# curveTracerRev4.net
KiCad netlist of a schematic drawn in EAGLE
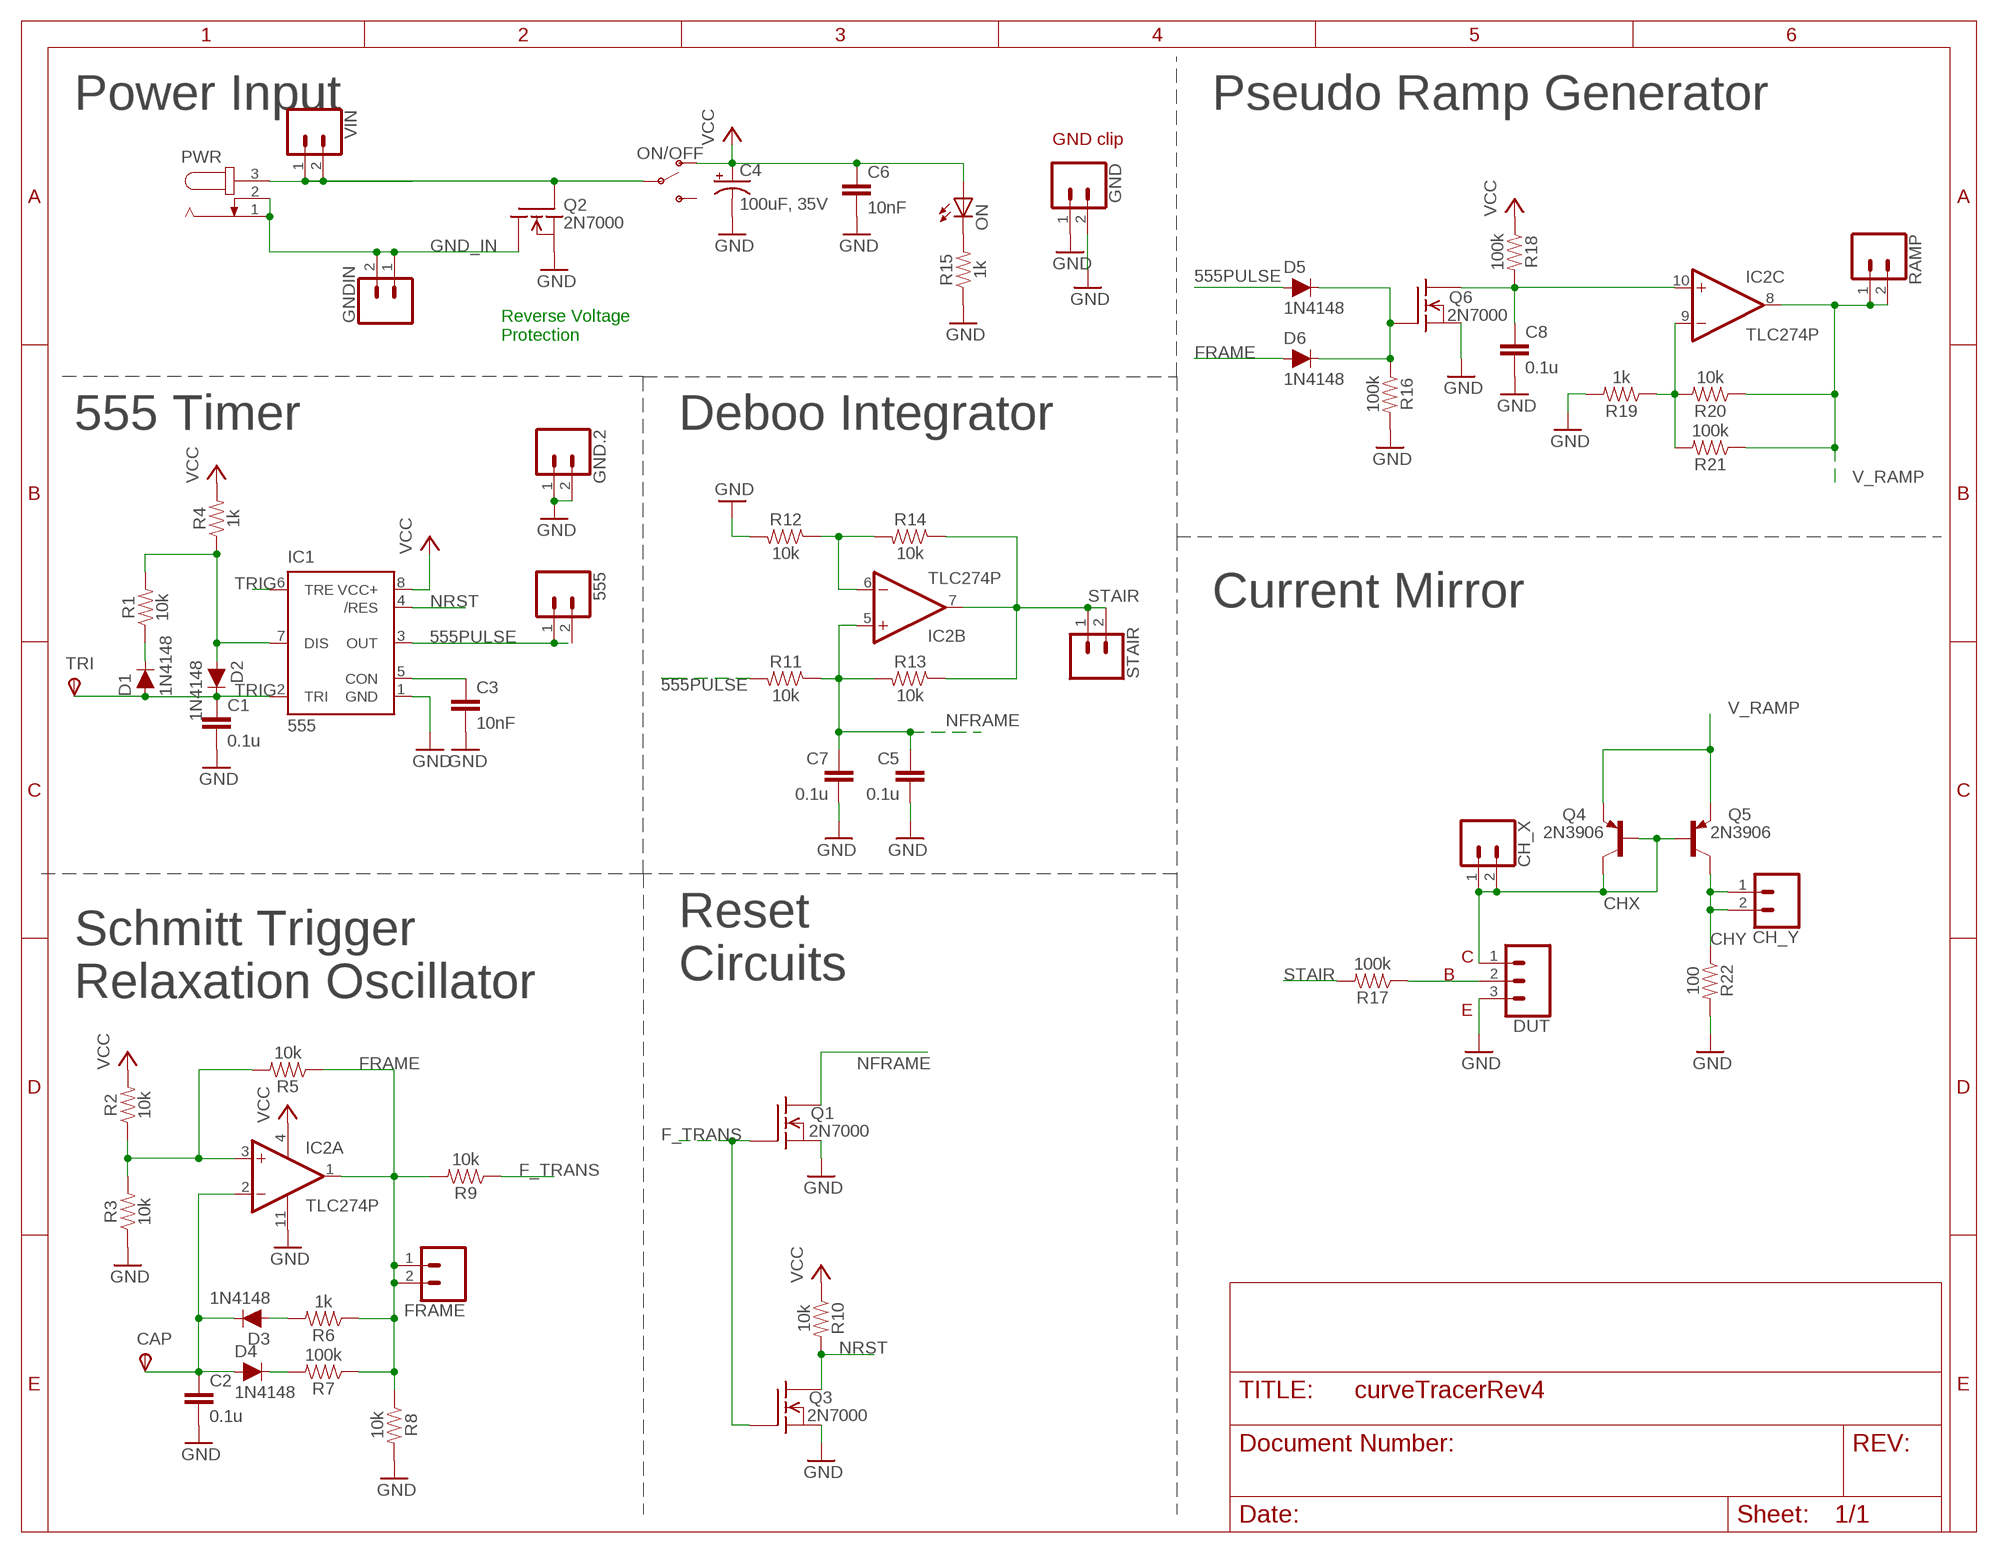
[diagram p0: schematic, sheet 1]

(export (version "E")
  (design (tool "Eeschema 10.0.6"))
  (components
    (comp (ref "555")
      (value "CONN_02")
      (footprint "eagle-import:1X02")
      (libsource (lib "eagle-import") (part "CONN_02"))
    )
    (comp (ref "C1")
      (value "0.1u")
      (footprint "eagle-import:C050-024X044")
      (libsource (lib "eagle-import") (part "C-EU050-024X044"))
    )
    (comp (ref "C2")
      (value "0.1u")
      (footprint "eagle-import:C050-024X044")
      (libsource (lib "eagle-import") (part "C-EU050-024X044"))
    )
    (comp (ref "C3")
      (value "10nF")
      (footprint "eagle-import:C050-024X044")
      (libsource (lib "eagle-import") (part "C-EU050-024X044"))
    )
    (comp (ref "C4")
      (value "100uF, 35V")
      (footprint "eagle-import:E2,5-6")
      (libsource (lib "eagle-import") (part "CPOL-USE2.5-6"))
    )
    (comp (ref "C5")
      (value "0.1u")
      (footprint "eagle-import:C050-024X044")
      (libsource (lib "eagle-import") (part "C-EU050-024X044"))
    )
    (comp (ref "C6")
      (value "10nF")
      (footprint "eagle-import:C050-024X044")
      (libsource (lib "eagle-import") (part "C-EU050-024X044"))
    )
    (comp (ref "C7")
      (value "0.1u")
      (footprint "eagle-import:C050-024X044")
      (libsource (lib "eagle-import") (part "C-EU050-024X044"))
    )
    (comp (ref "C8")
      (value "0.1u")
      (footprint "eagle-import:C050-024X044")
      (libsource (lib "eagle-import") (part "C-EU050-024X044"))
    )
    (comp (ref "CAP")
      (value "TPSPAD1-13Y")
      (footprint "eagle-import:P1-13Y")
      (libsource (lib "eagle-import") (part "TPSPAD1-13Y"))
    )
    (comp (ref "CH_X")
      (value "CONN_02")
      (footprint "eagle-import:1X02")
      (libsource (lib "eagle-import") (part "CONN_02"))
    )
    (comp (ref "CH_Y")
      (value "CONN_02")
      (footprint "eagle-import:1X02")
      (libsource (lib "eagle-import") (part "CONN_02"))
    )
    (comp (ref "D1")
      (value "1N4148")
      (footprint "eagle-import:DIODE-1N4148")
      (libsource (lib "eagle-import") (part "DIODE-1N4148"))
    )
    (comp (ref "D2")
      (value "1N4148")
      (footprint "eagle-import:DIODE-1N4148")
      (libsource (lib "eagle-import") (part "DIODE-1N4148"))
    )
    (comp (ref "D3")
      (value "1N4148")
      (footprint "eagle-import:DIODE-1N4148")
      (libsource (lib "eagle-import") (part "DIODE-1N4148"))
    )
    (comp (ref "D4")
      (value "1N4148")
      (footprint "eagle-import:DIODE-1N4148")
      (libsource (lib "eagle-import") (part "DIODE-1N4148"))
    )
    (comp (ref "D5")
      (value "1N4148")
      (footprint "eagle-import:DIODE-1N4148")
      (libsource (lib "eagle-import") (part "DIODE-1N4148"))
    )
    (comp (ref "D6")
      (value "1N4148")
      (footprint "eagle-import:DIODE-1N4148")
      (libsource (lib "eagle-import") (part "DIODE-1N4148"))
    )
    (comp (ref "DUT")
      (value "CONN_03LOCK_LONGPADS")
      (footprint "eagle-import:1X03_LOCK_LONGPADS")
      (libsource (lib "eagle-import") (part "CONN_03LOCK_LONGPADS"))
    )
    (comp (ref "FRAME")
      (value "CONN_02")
      (footprint "eagle-import:1X02")
      (libsource (lib "eagle-import") (part "CONN_02"))
    )
    (comp (ref "GND")
      (value "CONN_02")
      (footprint "eagle-import:1X02")
      (libsource (lib "eagle-import") (part "CONN_02"))
    )
    (comp (ref "GND.2")
      (value "CONN_02")
      (footprint "eagle-import:1X02")
      (libsource (lib "eagle-import") (part "CONN_02"))
    )
    (comp (ref "GNDIN")
      (value "CONN_02")
      (footprint "eagle-import:1X02")
      (libsource (lib "eagle-import") (part "CONN_02"))
    )
    (comp (ref "IC1")
      (value "555")
      (footprint "eagle-import:DIP08")
      (libsource (lib "eagle-import") (part "555P"))
    )
    (comp (ref "IC2")
      (value "TLC274P")
      (footprint "eagle-import:DIL14")
      (libsource (lib "eagle-import") (part "TLC274P"))
    )
    (comp (ref "ON")
      (value "LED5MM")
      (footprint "eagle-import:LED5MM")
      (libsource (lib "eagle-import") (part "LED5MM"))
    )
    (comp (ref "ON/OFF")
      (value "SWITCH-SPDT-PTH-11.6X4.0MM")
      (footprint "eagle-import:SWITCH_SPDT_PTH_11.6X4.0MM")
      (libsource (lib "eagle-import") (part "SWITCH-SPDT-PTH-11.6X4.0MM"))
    )
    (comp (ref "PWR")
      (value "JACK-PLUG0")
      (footprint "eagle-import:SPC4077")
      (libsource (lib "eagle-import") (part "JACK-PLUG0"))
    )
    (comp (ref "Q1")
      (value "2N7000")
      (footprint "eagle-import:TO-92")
      (libsource (lib "eagle-import") (part "TN0602N3"))
    )
    (comp (ref "Q2")
      (value "2N7000")
      (footprint "eagle-import:TO-92")
      (libsource (lib "eagle-import") (part "TN0602N3"))
    )
    (comp (ref "Q3")
      (value "2N7000")
      (footprint "eagle-import:TO-92")
      (libsource (lib "eagle-import") (part "TN0602N3"))
    )
    (comp (ref "Q4")
      (value "2N3906")
      (footprint "eagle-import:TO92")
      (libsource (lib "eagle-import") (part "2N3906"))
    )
    (comp (ref "Q5")
      (value "2N3906")
      (footprint "eagle-import:TO92")
      (libsource (lib "eagle-import") (part "2N3906"))
    )
    (comp (ref "Q6")
      (value "2N7000")
      (footprint "eagle-import:TO-92")
      (libsource (lib "eagle-import") (part "TN0602N3"))
    )
    (comp (ref "R1")
      (value "10k")
      (footprint "eagle-import:AXIAL-0.3")
      (libsource (lib "eagle-import") (part "RESISTORAXIAL-0.3"))
    )
    (comp (ref "R2")
      (value "10k")
      (footprint "eagle-import:AXIAL-0.3")
      (libsource (lib "eagle-import") (part "RESISTORAXIAL-0.3"))
    )
    (comp (ref "R3")
      (value "10k")
      (footprint "eagle-import:AXIAL-0.3")
      (libsource (lib "eagle-import") (part "RESISTORAXIAL-0.3"))
    )
    (comp (ref "R4")
      (value "1k")
      (footprint "eagle-import:AXIAL-0.3")
      (libsource (lib "eagle-import") (part "RESISTORAXIAL-0.3"))
    )
    (comp (ref "R5")
      (value "10k")
      (footprint "eagle-import:AXIAL-0.3")
      (libsource (lib "eagle-import") (part "RESISTORAXIAL-0.3"))
    )
    (comp (ref "R6")
      (value "1k")
      (footprint "eagle-import:AXIAL-0.3")
      (libsource (lib "eagle-import") (part "RESISTORAXIAL-0.3"))
    )
    (comp (ref "R7")
      (value "100k")
      (footprint "eagle-import:AXIAL-0.3")
      (libsource (lib "eagle-import") (part "RESISTORAXIAL-0.3"))
    )
    (comp (ref "R8")
      (value "10k")
      (footprint "eagle-import:AXIAL-0.3")
      (libsource (lib "eagle-import") (part "RESISTORAXIAL-0.3"))
    )
    (comp (ref "R9")
      (value "10k")
      (footprint "eagle-import:AXIAL-0.3")
      (libsource (lib "eagle-import") (part "RESISTORAXIAL-0.3"))
    )
    (comp (ref "R10")
      (value "10k")
      (footprint "eagle-import:AXIAL-0.3")
      (libsource (lib "eagle-import") (part "RESISTORAXIAL-0.3"))
    )
    (comp (ref "R11")
      (value "10k")
      (footprint "eagle-import:AXIAL-0.3")
      (libsource (lib "eagle-import") (part "RESISTORAXIAL-0.3"))
    )
    (comp (ref "R12")
      (value "10k")
      (footprint "eagle-import:AXIAL-0.3")
      (libsource (lib "eagle-import") (part "RESISTORAXIAL-0.3"))
    )
    (comp (ref "R13")
      (value "10k")
      (footprint "eagle-import:AXIAL-0.3")
      (libsource (lib "eagle-import") (part "RESISTORAXIAL-0.3"))
    )
    (comp (ref "R14")
      (value "10k")
      (footprint "eagle-import:AXIAL-0.3")
      (libsource (lib "eagle-import") (part "RESISTORAXIAL-0.3"))
    )
    (comp (ref "R15")
      (value "1k")
      (footprint "eagle-import:AXIAL-0.3")
      (libsource (lib "eagle-import") (part "RESISTORAXIAL-0.3"))
    )
    (comp (ref "R16")
      (value "100k")
      (footprint "eagle-import:AXIAL-0.3")
      (libsource (lib "eagle-import") (part "RESISTORAXIAL-0.3"))
    )
    (comp (ref "R17")
      (value "100k")
      (footprint "eagle-import:AXIAL-0.3")
      (libsource (lib "eagle-import") (part "RESISTORAXIAL-0.3"))
    )
    (comp (ref "R18")
      (value "100k")
      (footprint "eagle-import:AXIAL-0.3")
      (libsource (lib "eagle-import") (part "RESISTORAXIAL-0.3"))
    )
    (comp (ref "R19")
      (value "1k")
      (footprint "eagle-import:AXIAL-0.3")
      (libsource (lib "eagle-import") (part "RESISTORAXIAL-0.3"))
    )
    (comp (ref "R20")
      (value "10k")
      (footprint "eagle-import:AXIAL-0.3")
      (libsource (lib "eagle-import") (part "RESISTORAXIAL-0.3"))
    )
    (comp (ref "R21")
      (value "100k")
      (footprint "eagle-import:AXIAL-0.3")
      (libsource (lib "eagle-import") (part "RESISTORAXIAL-0.3"))
    )
    (comp (ref "R22")
      (value "100")
      (footprint "eagle-import:AXIAL-0.3")
      (libsource (lib "eagle-import") (part "RESISTORAXIAL-0.3"))
    )
    (comp (ref "RAMP")
      (value "CONN_02")
      (footprint "eagle-import:1X02")
      (libsource (lib "eagle-import") (part "CONN_02"))
    )
    (comp (ref "STAIR")
      (value "CONN_02")
      (footprint "eagle-import:1X02")
      (libsource (lib "eagle-import") (part "CONN_02"))
    )
    (comp (ref "TRI")
      (value "TPSPAD1-13Y")
      (footprint "eagle-import:P1-13Y")
      (libsource (lib "eagle-import") (part "TPSPAD1-13Y"))
    )
    (comp (ref "VIN")
      (value "CONN_02")
      (footprint "eagle-import:1X02")
      (libsource (lib "eagle-import") (part "CONN_02"))
    )
  )
  (nets
    (net (code "1") (name "/555PULSE") (class "Default")
      (node (ref "555") (pin "1") (pinfunction "1_1") (pintype "passive"))
      (node (ref "555") (pin "2") (pinfunction "2_2") (pintype "passive"))
      (node (ref "D5") (pin "A") (pinfunction "A_A") (pintype "passive"))
      (node (ref "IC1") (pin "3") (pinfunction "OUT_3") (pintype "output"))
      (node (ref "R11") (pin "P$2") (pinfunction "2_P$2") (pintype "passive"))
    )
    (net (code "2") (name "/CHX") (class "Default")
      (node (ref "CH_X") (pin "1") (pinfunction "1_1") (pintype "passive"))
      (node (ref "CH_X") (pin "2") (pinfunction "2_2") (pintype "passive"))
      (node (ref "DUT") (pin "1") (pinfunction "1_1") (pintype "passive"))
      (node (ref "Q4") (pin "1") (pinfunction "C_1") (pintype "passive"))
      (node (ref "Q4") (pin "2") (pinfunction "B_2") (pintype "passive"))
      (node (ref "Q5") (pin "2") (pinfunction "B_2") (pintype "passive"))
    )
    (net (code "3") (name "/CHY") (class "Default")
      (node (ref "CH_Y") (pin "1") (pinfunction "1_1") (pintype "passive"))
      (node (ref "CH_Y") (pin "2") (pinfunction "2_2") (pintype "passive"))
      (node (ref "Q5") (pin "1") (pinfunction "C_1") (pintype "passive"))
      (node (ref "R22") (pin "P$1") (pinfunction "1_P$1") (pintype "passive"))
    )
    (net (code "4") (name "/FRAME") (class "Default")
      (node (ref "D6") (pin "A") (pinfunction "A_A") (pintype "passive"))
      (node (ref "FRAME") (pin "1") (pinfunction "1_1") (pintype "passive"))
      (node (ref "FRAME") (pin "2") (pinfunction "2_2") (pintype "passive"))
      (node (ref "IC2") (pin "1") (pinfunction "OUT_1") (pintype "output"))
      (node (ref "R5") (pin "P$1") (pinfunction "1_P$1") (pintype "passive"))
      (node (ref "R6") (pin "P$1") (pinfunction "1_P$1") (pintype "passive"))
      (node (ref "R7") (pin "P$1") (pinfunction "1_P$1") (pintype "passive"))
      (node (ref "R8") (pin "P$1") (pinfunction "1_P$1") (pintype "passive"))
      (node (ref "R9") (pin "P$2") (pinfunction "2_P$2") (pintype "passive"))
    )
    (net (code "5") (name "/F_TRANS") (class "Default")
      (node (ref "Q1") (pin "2") (pinfunction "G_2") (pintype "passive"))
      (node (ref "Q3") (pin "2") (pinfunction "G_2") (pintype "passive"))
      (node (ref "R9") (pin "P$1") (pinfunction "1_P$1") (pintype "passive"))
    )
    (net (code "6") (name "/GND_IN") (class "Default")
      (node (ref "GNDIN") (pin "1") (pinfunction "1_1") (pintype "passive"))
      (node (ref "GNDIN") (pin "2") (pinfunction "2_2") (pintype "passive"))
      (node (ref "PWR") (pin "1") (pinfunction "1_1") (pintype "passive"))
      (node (ref "PWR") (pin "2") (pinfunction "2_2") (pintype "passive"))
      (node (ref "Q2") (pin "3") (pinfunction "D_3") (pintype "passive"))
    )
    (net (code "7") (name "/NFRAME") (class "Default")
      (node (ref "C5") (pin "1") (pinfunction "1_1") (pintype "passive"))
      (node (ref "C7") (pin "1") (pinfunction "1_1") (pintype "passive"))
      (node (ref "IC2") (pin "5") (pinfunction "+IN_5") (pintype "input"))
      (node (ref "Q1") (pin "3") (pinfunction "D_3") (pintype "passive"))
      (node (ref "R11") (pin "P$1") (pinfunction "1_P$1") (pintype "passive"))
      (node (ref "R13") (pin "P$2") (pinfunction "2_P$2") (pintype "passive"))
    )
    (net (code "8") (name "/NRST") (class "Default")
      (node (ref "IC1") (pin "4") (pinfunction "/RES_4") (pintype "input"))
      (node (ref "Q3") (pin "3") (pinfunction "D_3") (pintype "passive"))
      (node (ref "R10") (pin "P$2") (pinfunction "2_P$2") (pintype "passive"))
    )
    (net (code "9") (name "/STAIR") (class "Default")
      (node (ref "IC2") (pin "7") (pinfunction "OUT_7") (pintype "output"))
      (node (ref "R13") (pin "P$1") (pinfunction "1_P$1") (pintype "passive"))
      (node (ref "R14") (pin "P$1") (pinfunction "1_P$1") (pintype "passive"))
      (node (ref "R17") (pin "P$2") (pinfunction "2_P$2") (pintype "passive"))
      (node (ref "STAIR") (pin "1") (pinfunction "1_1") (pintype "passive"))
      (node (ref "STAIR") (pin "2") (pinfunction "2_2") (pintype "passive"))
    )
    (net (code "10") (name "/TRIG") (class "Default")
      (node (ref "C1") (pin "1") (pinfunction "1_1") (pintype "passive"))
      (node (ref "D1") (pin "A") (pinfunction "A_A") (pintype "passive"))
      (node (ref "D2") (pin "C") (pinfunction "C_C") (pintype "passive"))
      (node (ref "IC1") (pin "2") (pinfunction "TRI_2") (pintype "input"))
      (node (ref "IC1") (pin "6") (pinfunction "TRE_6") (pintype "input"))
      (node (ref "TRI") (pin "TP") (pinfunction "PP_TP") (pintype "input"))
    )
    (net (code "11") (name "/V_RAMP") (class "Default")
      (node (ref "IC2") (pin "8") (pinfunction "OUT_8") (pintype "output"))
      (node (ref "Q4") (pin "3") (pinfunction "E_3") (pintype "passive"))
      (node (ref "Q5") (pin "3") (pinfunction "E_3") (pintype "passive"))
      (node (ref "R20") (pin "P$1") (pinfunction "1_P$1") (pintype "passive"))
      (node (ref "R21") (pin "P$1") (pinfunction "1_P$1") (pintype "passive"))
      (node (ref "RAMP") (pin "1") (pinfunction "1_1") (pintype "passive"))
      (node (ref "RAMP") (pin "2") (pinfunction "2_2") (pintype "passive"))
    )
    (net (code "12") (name "GND") (class "Default")
      (node (ref "C1") (pin "2") (pinfunction "2_2") (pintype "passive"))
      (node (ref "C2") (pin "2") (pinfunction "2_2") (pintype "passive"))
      (node (ref "C3") (pin "2") (pinfunction "2_2") (pintype "passive"))
      (node (ref "C4") (pin "-") (pinfunction "-_-") (pintype "passive"))
      (node (ref "C5") (pin "2") (pinfunction "2_2") (pintype "passive"))
      (node (ref "C6") (pin "2") (pinfunction "2_2") (pintype "passive"))
      (node (ref "C7") (pin "2") (pinfunction "2_2") (pintype "passive"))
      (node (ref "C8") (pin "2") (pinfunction "2_2") (pintype "passive"))
      (node (ref "DUT") (pin "3") (pinfunction "3_3") (pintype "passive"))
      (node (ref "GND") (pin "1") (pinfunction "1_1") (pintype "passive"))
      (node (ref "GND") (pin "2") (pinfunction "2_2") (pintype "passive"))
      (node (ref "GND.2") (pin "1") (pinfunction "1_1") (pintype "passive"))
      (node (ref "GND.2") (pin "2") (pinfunction "2_2") (pintype "passive"))
      (node (ref "IC1") (pin "1") (pinfunction "GND_1") (pintype "power_in"))
      (node (ref "IC2") (pin "11") (pinfunction "V-_11") (pintype "power_in"))
      (node (ref "Q1") (pin "1") (pinfunction "S_1") (pintype "passive"))
      (node (ref "Q2") (pin "1") (pinfunction "S_1") (pintype "passive"))
      (node (ref "Q3") (pin "1") (pinfunction "S_1") (pintype "passive"))
      (node (ref "Q6") (pin "1") (pinfunction "S_1") (pintype "passive"))
      (node (ref "R12") (pin "P$2") (pinfunction "2_P$2") (pintype "passive"))
      (node (ref "R15") (pin "P$1") (pinfunction "1_P$1") (pintype "passive"))
      (node (ref "R16") (pin "P$2") (pinfunction "2_P$2") (pintype "passive"))
      (node (ref "R19") (pin "P$2") (pinfunction "2_P$2") (pintype "passive"))
      (node (ref "R22") (pin "P$2") (pinfunction "2_P$2") (pintype "passive"))
      (node (ref "R3") (pin "P$1") (pinfunction "1_P$1") (pintype "passive"))
      (node (ref "R8") (pin "P$2") (pinfunction "2_P$2") (pintype "passive"))
    )
    (net (code "13") (name "Net-(CAP-PP)") (class "Default")
      (node (ref "C2") (pin "1") (pinfunction "1_1") (pintype "passive"))
      (node (ref "CAP") (pin "TP") (pinfunction "PP_TP") (pintype "input"))
      (node (ref "D3") (pin "C") (pinfunction "C_C") (pintype "passive"))
      (node (ref "D4") (pin "A") (pinfunction "A_A") (pintype "passive"))
      (node (ref "IC2") (pin "2") (pinfunction "-IN_2") (pintype "input"))
    )
    (net (code "14") (name "Net-(IC1-CON)") (class "Default")
      (node (ref "C3") (pin "1") (pinfunction "1_1") (pintype "passive"))
      (node (ref "IC1") (pin "5") (pinfunction "CON_5") (pintype "input"))
    )
    (net (code "15") (name "Net-(IC1-DIS)") (class "Default")
      (node (ref "D2") (pin "A") (pinfunction "A_A") (pintype "passive"))
      (node (ref "IC1") (pin "7") (pinfunction "DIS_7") (pintype "input"))
      (node (ref "R1") (pin "P$2") (pinfunction "2_P$2") (pintype "passive"))
      (node (ref "R4") (pin "P$1") (pinfunction "1_P$1") (pintype "passive"))
    )
    (net (code "16") (name "Net-(IC2A-+IN)") (class "Default")
      (node (ref "IC2") (pin "3") (pinfunction "+IN_3") (pintype "input"))
      (node (ref "R2") (pin "P$1") (pinfunction "1_P$1") (pintype "passive"))
      (node (ref "R3") (pin "P$2") (pinfunction "2_P$2") (pintype "passive"))
      (node (ref "R5") (pin "P$2") (pinfunction "2_P$2") (pintype "passive"))
    )
    (net (code "17") (name "Net-(IC2B--IN)") (class "Default")
      (node (ref "IC2") (pin "6") (pinfunction "-IN_6") (pintype "input"))
      (node (ref "R12") (pin "P$1") (pinfunction "1_P$1") (pintype "passive"))
      (node (ref "R14") (pin "P$2") (pinfunction "2_P$2") (pintype "passive"))
    )
    (net (code "18") (name "Net-(IC2C-+IN)") (class "Default")
      (node (ref "C8") (pin "1") (pinfunction "1_1") (pintype "passive"))
      (node (ref "IC2") (pin "10") (pinfunction "+IN_10") (pintype "input"))
      (node (ref "Q6") (pin "3") (pinfunction "D_3") (pintype "passive"))
      (node (ref "R18") (pin "P$2") (pinfunction "2_P$2") (pintype "passive"))
    )
    (net (code "19") (name "Net-(IC2C--IN)") (class "Default")
      (node (ref "IC2") (pin "9") (pinfunction "-IN_9") (pintype "input"))
      (node (ref "R19") (pin "P$1") (pinfunction "1_P$1") (pintype "passive"))
      (node (ref "R20") (pin "P$2") (pinfunction "2_P$2") (pintype "passive"))
      (node (ref "R21") (pin "P$2") (pinfunction "2_P$2") (pintype "passive"))
    )
    (net (code "20") (name "Net-(ON-C)") (class "Default")
      (node (ref "ON") (pin "K") (pinfunction "C_K") (pintype "passive"))
      (node (ref "R15") (pin "P$2") (pinfunction "2_P$2") (pintype "passive"))
    )
    (net (code "21") (name "Net-(ON/OFF-P)") (class "Default")
      (node (ref "ON/OFF") (pin "2") (pinfunction "P_2") (pintype "passive"))
      (node (ref "PWR") (pin "3") (pinfunction "3_3") (pintype "passive"))
      (node (ref "Q2") (pin "2") (pinfunction "G_2") (pintype "passive"))
      (node (ref "VIN") (pin "1") (pinfunction "1_1") (pintype "passive"))
      (node (ref "VIN") (pin "2") (pinfunction "2_2") (pintype "passive"))
    )
    (net (code "22") (name "Net-(Q6-G)") (class "Default")
      (node (ref "D5") (pin "C") (pinfunction "C_C") (pintype "passive"))
      (node (ref "D6") (pin "C") (pinfunction "C_C") (pintype "passive"))
      (node (ref "Q6") (pin "2") (pinfunction "G_2") (pintype "passive"))
      (node (ref "R16") (pin "P$1") (pinfunction "1_P$1") (pintype "passive"))
    )
    (net (code "23") (name "Net-(R1-1)") (class "Default")
      (node (ref "D1") (pin "C") (pinfunction "C_C") (pintype "passive"))
      (node (ref "R1") (pin "P$1") (pinfunction "1_P$1") (pintype "passive"))
    )
    (net (code "24") (name "Net-(R6-2)") (class "Default")
      (node (ref "D3") (pin "A") (pinfunction "A_A") (pintype "passive"))
      (node (ref "R6") (pin "P$2") (pinfunction "2_P$2") (pintype "passive"))
    )
    (net (code "25") (name "Net-(R7-2)") (class "Default")
      (node (ref "D4") (pin "C") (pinfunction "C_C") (pintype "passive"))
      (node (ref "R7") (pin "P$2") (pinfunction "2_P$2") (pintype "passive"))
    )
    (net (code "26") (name "Net-(R17-1)") (class "Default")
      (node (ref "DUT") (pin "2") (pinfunction "2_2") (pintype "passive"))
      (node (ref "R17") (pin "P$1") (pinfunction "1_P$1") (pintype "passive"))
    )
    (net (code "27") (name "VCC") (class "Default")
      (node (ref "C4") (pin "+") (pinfunction "+_+") (pintype "passive"))
      (node (ref "C6") (pin "1") (pinfunction "1_1") (pintype "passive"))
      (node (ref "IC1") (pin "8") (pinfunction "VCC+_8") (pintype "power_in"))
      (node (ref "IC2") (pin "4") (pinfunction "V+_4") (pintype "power_in"))
      (node (ref "ON") (pin "A") (pinfunction "A_A") (pintype "passive"))
      (node (ref "ON/OFF") (pin "1") (pinfunction "O_1") (pintype "passive"))
      (node (ref "R10") (pin "P$1") (pinfunction "1_P$1") (pintype "passive"))
      (node (ref "R18") (pin "P$1") (pinfunction "1_P$1") (pintype "passive"))
      (node (ref "R2") (pin "P$2") (pinfunction "2_P$2") (pintype "passive"))
      (node (ref "R4") (pin "P$2") (pinfunction "2_P$2") (pintype "passive"))
    )
    (net (code "28") (name "unconnected-(ON/OFF-S-Pad3)") (class "Default")
      (node (ref "ON/OFF") (pin "3") (pinfunction "S_3") (pintype "passive"))
    )
  )
)
